# ST1-100-Top.net
KiCad netlist of a schematic drawn in Altium Designer
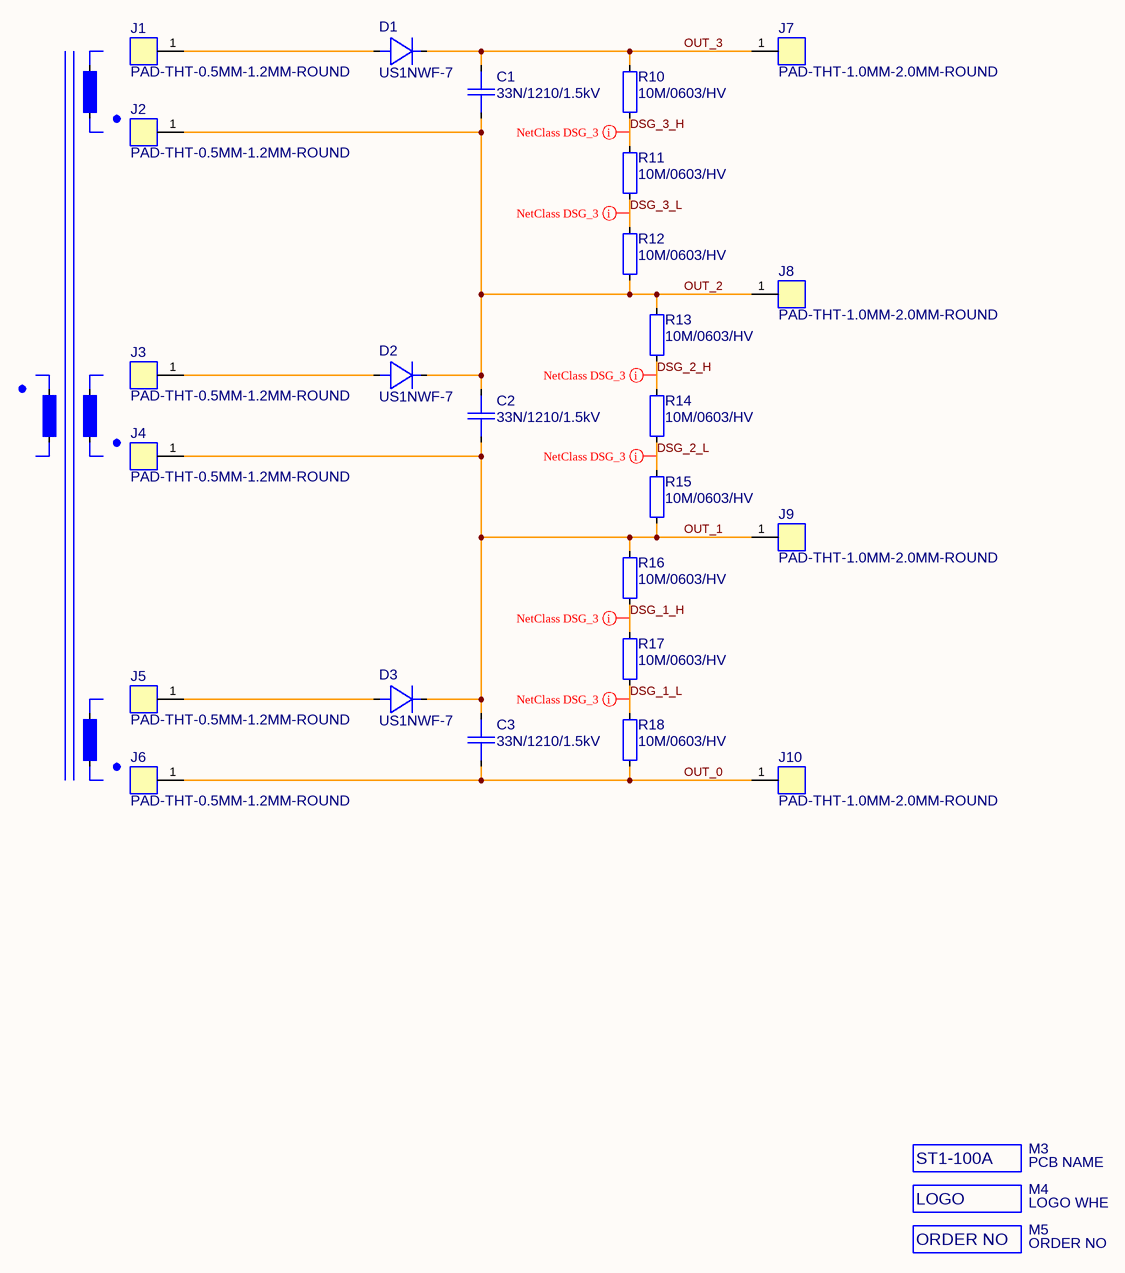
[diagram p0: ST1-100-Top.SchDoc]

(export (version "E")
  (design (tool "Eeschema 10.0.6"))
  (components
    (comp (ref "C1")
      (value "33N/1210/1.5kV")
      (footprint "CAP1210_X7R")
      (description "CAP SM 1210 33nF 1.5kV")
      (fields (field (name "MANUFACTURER") "GENERIC"))
      (libsource (lib "daniw_altium_lib") (part "C"))
    )
    (comp (ref "C2")
      (value "33N/1210/1.5kV")
      (footprint "CAP1210_X7R")
      (description "CAP SM 1210 33nF 1.5kV")
      (fields (field (name "MANUFACTURER") "GENERIC"))
      (libsource (lib "daniw_altium_lib") (part "C"))
    )
    (comp (ref "C3")
      (value "33N/1210/1.5kV")
      (footprint "CAP1210_X7R")
      (description "CAP SM 1210 33nF 1.5kV")
      (fields (field (name "MANUFACTURER") "GENERIC"))
      (libsource (lib "daniw_altium_lib") (part "C"))
    )
    (comp (ref "D1")
      (value "US1NWF-7")
      (footprint "SOD3718X125")
      (description "US1NWF 1.0A SURFACE MOUNT ULTRA-FAST RECTIFIER")
      (fields (field (name "MANUFACTURER") "Diodes Incorporated"))
      (libsource (lib "daniw_altium_lib") (part "D"))
    )
    (comp (ref "D2")
      (value "US1NWF-7")
      (footprint "SOD3718X125")
      (description "US1NWF 1.0A SURFACE MOUNT ULTRA-FAST RECTIFIER")
      (fields (field (name "MANUFACTURER") "Diodes Incorporated"))
      (libsource (lib "daniw_altium_lib") (part "D"))
    )
    (comp (ref "D3")
      (value "US1NWF-7")
      (footprint "SOD3718X125")
      (description "US1NWF 1.0A SURFACE MOUNT ULTRA-FAST RECTIFIER")
      (fields (field (name "MANUFACTURER") "Diodes Incorporated"))
      (libsource (lib "daniw_altium_lib") (part "D"))
    )
    (comp (ref "J1")
      (value "PAD-THT-0.5MM-1.2MM-ROUND")
      (footprint "PAD-THT-0.5MM-1.2MM-ROUND")
      (description "Through-hole pad, 0.5mm drill, 1.2mm pad, round")
      (fields (field (name "MANUFACTURER") "GENERIC"))
      (libsource (lib "") (part "CON1_1"))
    )
    (comp (ref "J2")
      (value "PAD-THT-0.5MM-1.2MM-ROUND")
      (footprint "PAD-THT-0.5MM-1.2MM-ROUND")
      (description "Through-hole pad, 0.5mm drill, 1.2mm pad, round")
      (fields (field (name "MANUFACTURER") "GENERIC"))
      (libsource (lib "") (part "CON1_1"))
    )
    (comp (ref "J3")
      (value "PAD-THT-0.5MM-1.2MM-ROUND")
      (footprint "PAD-THT-0.5MM-1.2MM-ROUND")
      (description "Through-hole pad, 0.5mm drill, 1.2mm pad, round")
      (fields (field (name "MANUFACTURER") "GENERIC"))
      (libsource (lib "") (part "CON1_1"))
    )
    (comp (ref "J4")
      (value "PAD-THT-0.5MM-1.2MM-ROUND")
      (footprint "PAD-THT-0.5MM-1.2MM-ROUND")
      (description "Through-hole pad, 0.5mm drill, 1.2mm pad, round")
      (fields (field (name "MANUFACTURER") "GENERIC"))
      (libsource (lib "") (part "CON1_1"))
    )
    (comp (ref "J5")
      (value "PAD-THT-0.5MM-1.2MM-ROUND")
      (footprint "PAD-THT-0.5MM-1.2MM-ROUND")
      (description "Through-hole pad, 0.5mm drill, 1.2mm pad, round")
      (fields (field (name "MANUFACTURER") "GENERIC"))
      (libsource (lib "") (part "CON1_1"))
    )
    (comp (ref "J6")
      (value "PAD-THT-0.5MM-1.2MM-ROUND")
      (footprint "PAD-THT-0.5MM-1.2MM-ROUND")
      (description "Through-hole pad, 0.5mm drill, 1.2mm pad, round")
      (fields (field (name "MANUFACTURER") "GENERIC"))
      (libsource (lib "") (part "CON1_1"))
    )
    (comp (ref "J7")
      (value "PAD-THT-1.0MM-2.0MM-ROUND")
      (footprint "PAD-THT-1.0MM-2.0MM-ROUND")
      (description "Through-hole pad, 1.0mm drill, 2.0mm pad, round")
      (fields (field (name "MANUFACTURER") "GENERIC"))
      (libsource (lib "daniw_altium_lib") (part "CON1"))
    )
    (comp (ref "J8")
      (value "PAD-THT-1.0MM-2.0MM-ROUND")
      (footprint "PAD-THT-1.0MM-2.0MM-ROUND")
      (description "Through-hole pad, 1.0mm drill, 2.0mm pad, round")
      (fields (field (name "MANUFACTURER") "GENERIC"))
      (libsource (lib "daniw_altium_lib") (part "CON1"))
    )
    (comp (ref "J9")
      (value "PAD-THT-1.0MM-2.0MM-ROUND")
      (footprint "PAD-THT-1.0MM-2.0MM-ROUND")
      (description "Through-hole pad, 1.0mm drill, 2.0mm pad, round")
      (fields (field (name "MANUFACTURER") "GENERIC"))
      (libsource (lib "daniw_altium_lib") (part "CON1"))
    )
    (comp (ref "J10")
      (value "PAD-THT-1.0MM-2.0MM-ROUND")
      (footprint "PAD-THT-1.0MM-2.0MM-ROUND")
      (description "Through-hole pad, 1.0mm drill, 2.0mm pad, round")
      (fields (field (name "MANUFACTURER") "GENERIC"))
      (libsource (lib "daniw_altium_lib") (part "CON1"))
    )
    (comp (ref "L1")
      (value "22U~{H}7643")
      (description "FIXED IND 22UH 1.75A 92.5MOHM SM")
      (libsource (lib "") (part "L_1"))
    )
    (comp (ref "L2")
      (value "22U~{H}7643")
      (description "FIXED IND 22UH 1.75A 92.5MOHM SM")
      (libsource (lib "daniw_altium_lib") (part "L"))
    )
    (comp (ref "L3")
      (value "22U~{H}7643")
      (description "FIXED IND 22UH 1.75A 92.5MOHM SM")
      (libsource (lib "daniw_altium_lib") (part "L"))
    )
    (comp (ref "L4")
      (value "22U~{H}7643")
      (description "FIXED IND 22UH 1.75A 92.5MOHM SM")
      (libsource (lib "daniw_altium_lib") (part "L"))
    )
    (comp (ref "M3")
      (value "PCB NAME")
      (footprint "PCB-NAME-2MM-CENTER")
      (description "PCB name, 2mm text height, centered")
      (fields (field (name "PART NUMBER") "PCB NAME 2mm C") (field (name "MANUFACTURER") "NONE"))
      (libsource (lib "daniw_altium_lib") (part "PCB-NAME"))
    )
    (comp (ref "M4")
      (value "LOGO WHE")
      (footprint "LOGO-WHE-2MM")
      (description "WHE logo, size 2mm")
      (fields (field (name "PART NUMBER") "LOGO WHE 2MM") (field (name "MANUFACTURER") "NONE"))
      (libsource (lib "daniw_altium_lib") (part "LOGO"))
    )
    (comp (ref "M5")
      (value "ORDER NO")
      (footprint "JLC-ORDER")
      (description "Order number, JLC as per requirement")
      (fields (field (name "PART NUMBER") "ORDER NO JLC") (field (name "MANUFACTURER") "NONE"))
      (libsource (lib "daniw_altium_lib") (part "ORDER-NO"))
    )
    (comp (ref "R10")
      (value "10M/0603/HV")
      (footprint "R0603-0.40-WW")
      (description "RES SM 0603 10M High voltage")
      (fields (field (name "MANUFACTURER") "GENERIC"))
      (libsource (lib "daniw_altium_lib") (part "R"))
    )
    (comp (ref "R11")
      (value "10M/0603/HV")
      (footprint "R0603-0.40-WW")
      (description "RES SM 0603 10M High voltage")
      (fields (field (name "MANUFACTURER") "GENERIC"))
      (libsource (lib "daniw_altium_lib") (part "R"))
    )
    (comp (ref "R12")
      (value "10M/0603/HV")
      (footprint "R0603-0.40-WW")
      (description "RES SM 0603 10M High voltage")
      (fields (field (name "MANUFACTURER") "GENERIC"))
      (libsource (lib "daniw_altium_lib") (part "R"))
    )
    (comp (ref "R13")
      (value "10M/0603/HV")
      (footprint "R0603-0.40-WW")
      (description "RES SM 0603 10M High voltage")
      (fields (field (name "MANUFACTURER") "GENERIC"))
      (libsource (lib "daniw_altium_lib") (part "R"))
    )
    (comp (ref "R14")
      (value "10M/0603/HV")
      (footprint "R0603-0.40-WW")
      (description "RES SM 0603 10M High voltage")
      (fields (field (name "MANUFACTURER") "GENERIC"))
      (libsource (lib "daniw_altium_lib") (part "R"))
    )
    (comp (ref "R15")
      (value "10M/0603/HV")
      (footprint "R0603-0.40-WW")
      (description "RES SM 0603 10M High voltage")
      (fields (field (name "MANUFACTURER") "GENERIC"))
      (libsource (lib "daniw_altium_lib") (part "R"))
    )
    (comp (ref "R16")
      (value "10M/0603/HV")
      (footprint "R0603-0.40-WW")
      (description "RES SM 0603 10M High voltage")
      (fields (field (name "MANUFACTURER") "GENERIC"))
      (libsource (lib "daniw_altium_lib") (part "R"))
    )
    (comp (ref "R17")
      (value "10M/0603/HV")
      (footprint "R0603-0.40-WW")
      (description "RES SM 0603 10M High voltage")
      (fields (field (name "MANUFACTURER") "GENERIC"))
      (libsource (lib "daniw_altium_lib") (part "R"))
    )
    (comp (ref "R18")
      (value "10M/0603/HV")
      (footprint "R0603-0.40-WW")
      (description "RES SM 0603 10M High voltage")
      (fields (field (name "MANUFACTURER") "GENERIC"))
      (libsource (lib "daniw_altium_lib") (part "R"))
    )
  )
  (nets
    (net (code "1") (name "/DSG_1_H") (class "Default")
      (node (ref "R16") (pin "2") (pinfunction "2_2") (pintype "passive"))
      (node (ref "R17") (pin "1") (pinfunction "1_1") (pintype "passive"))
    )
    (net (code "2") (name "/DSG_1_L") (class "Default")
      (node (ref "R17") (pin "2") (pinfunction "2_2") (pintype "passive"))
      (node (ref "R18") (pin "1") (pinfunction "1_1") (pintype "passive"))
    )
    (net (code "3") (name "/DSG_2_H") (class "Default")
      (node (ref "R13") (pin "2") (pinfunction "2_2") (pintype "passive"))
      (node (ref "R14") (pin "1") (pinfunction "1_1") (pintype "passive"))
    )
    (net (code "4") (name "/DSG_2_L") (class "Default")
      (node (ref "R14") (pin "2") (pinfunction "2_2") (pintype "passive"))
      (node (ref "R15") (pin "1") (pinfunction "1_1") (pintype "passive"))
    )
    (net (code "5") (name "/DSG_3_H") (class "Default")
      (node (ref "R10") (pin "2") (pinfunction "2_2") (pintype "passive"))
      (node (ref "R11") (pin "1") (pinfunction "1_1") (pintype "passive"))
    )
    (net (code "6") (name "/DSG_3_L") (class "Default")
      (node (ref "R11") (pin "2") (pinfunction "2_2") (pintype "passive"))
      (node (ref "R12") (pin "1") (pinfunction "1_1") (pintype "passive"))
    )
    (net (code "7") (name "/OUT_0") (class "Default")
      (node (ref "C3") (pin "2") (pinfunction "2_2") (pintype "passive"))
      (node (ref "J10") (pin "1") (pintype "passive"))
      (node (ref "J6") (pin "1") (pintype "passive"))
      (node (ref "R18") (pin "2") (pinfunction "2_2") (pintype "passive"))
    )
    (net (code "8") (name "/OUT_1") (class "Default")
      (node (ref "C2") (pin "2") (pinfunction "2_2") (pintype "passive"))
      (node (ref "C3") (pin "1") (pinfunction "1_1") (pintype "passive"))
      (node (ref "D3") (pin "1") (pinfunction "C_1") (pintype "passive"))
      (node (ref "J4") (pin "1") (pintype "passive"))
      (node (ref "J9") (pin "1") (pintype "passive"))
      (node (ref "R15") (pin "2") (pinfunction "2_2") (pintype "passive"))
      (node (ref "R16") (pin "1") (pinfunction "1_1") (pintype "passive"))
    )
    (net (code "9") (name "/OUT_2") (class "Default")
      (node (ref "C1") (pin "2") (pinfunction "2_2") (pintype "passive"))
      (node (ref "C2") (pin "1") (pinfunction "1_1") (pintype "passive"))
      (node (ref "D2") (pin "1") (pinfunction "C_1") (pintype "passive"))
      (node (ref "J2") (pin "1") (pintype "passive"))
      (node (ref "J8") (pin "1") (pintype "passive"))
      (node (ref "R12") (pin "2") (pinfunction "2_2") (pintype "passive"))
      (node (ref "R13") (pin "1") (pinfunction "1_1") (pintype "passive"))
    )
    (net (code "10") (name "/OUT_3") (class "Default")
      (node (ref "C1") (pin "1") (pinfunction "1_1") (pintype "passive"))
      (node (ref "D1") (pin "1") (pinfunction "C_1") (pintype "passive"))
      (node (ref "J7") (pin "1") (pintype "passive"))
      (node (ref "R10") (pin "1") (pinfunction "1_1") (pintype "passive"))
    )
    (net (code "11") (name "Net-(D1-A)") (class "Default")
      (node (ref "D1") (pin "2") (pinfunction "A_2") (pintype "passive"))
      (node (ref "J1") (pin "1") (pintype "passive"))
    )
    (net (code "12") (name "Net-(D2-A)") (class "Default")
      (node (ref "D2") (pin "2") (pinfunction "A_2") (pintype "passive"))
      (node (ref "J3") (pin "1") (pintype "passive"))
    )
    (net (code "13") (name "Net-(D3-A)") (class "Default")
      (node (ref "D3") (pin "2") (pinfunction "A_2") (pintype "passive"))
      (node (ref "J5") (pin "1") (pintype "passive"))
    )
    (net (code "14") (name "unconnected-(L1-Pad1)") (class "Default")
      (node (ref "L1") (pin "1") (pinfunction "1_1") (pintype "passive"))
    )
    (net (code "15") (name "unconnected-(L1-Pad2)") (class "Default")
      (node (ref "L1") (pin "2") (pinfunction "2_2") (pintype "passive"))
    )
    (net (code "16") (name "unconnected-(L2-Pad1)") (class "Default")
      (node (ref "L2") (pin "1") (pinfunction "1_1") (pintype "passive"))
    )
    (net (code "17") (name "unconnected-(L2-Pad2)") (class "Default")
      (node (ref "L2") (pin "2") (pinfunction "2_2") (pintype "passive"))
    )
    (net (code "18") (name "unconnected-(L3-Pad1)") (class "Default")
      (node (ref "L3") (pin "1") (pinfunction "1_1") (pintype "passive"))
    )
    (net (code "19") (name "unconnected-(L3-Pad2)") (class "Default")
      (node (ref "L3") (pin "2") (pinfunction "2_2") (pintype "passive"))
    )
    (net (code "20") (name "unconnected-(L4-Pad1)") (class "Default")
      (node (ref "L4") (pin "1") (pinfunction "1_1") (pintype "passive"))
    )
    (net (code "21") (name "unconnected-(L4-Pad2)") (class "Default")
      (node (ref "L4") (pin "2") (pinfunction "2_2") (pintype "passive"))
    )
  )
)
